# Sheet1.net
KiCad netlist of a schematic drawn in Altium Designer
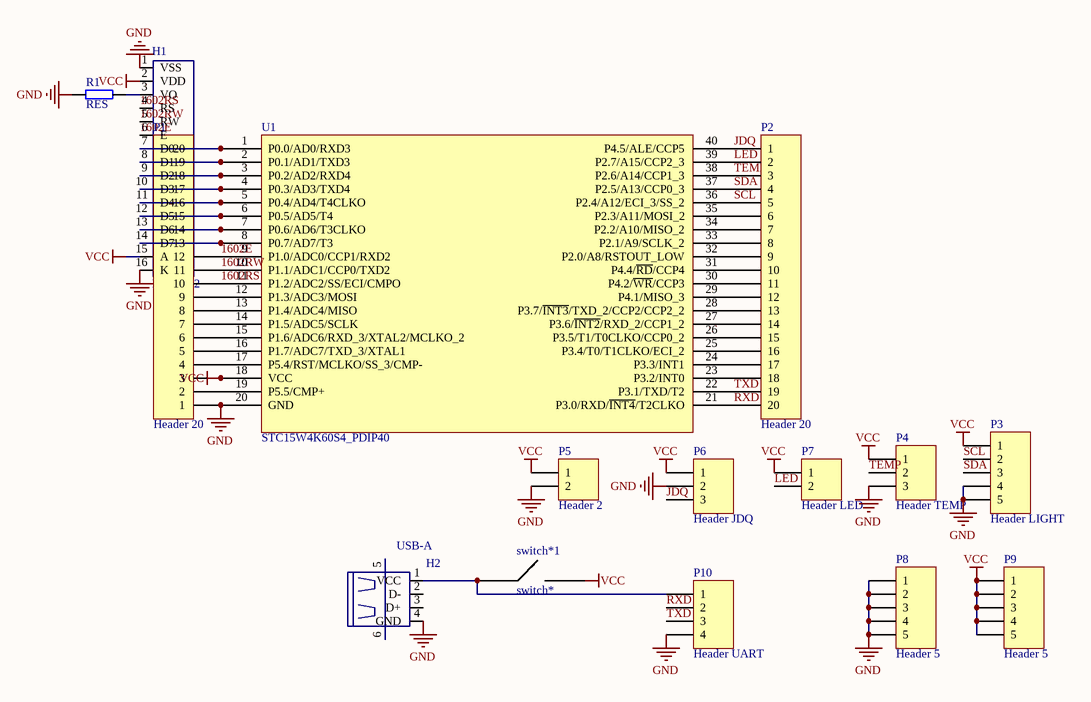
[diagram p0: Sheet1.SchDoc]

(export (version "E")
  (design (tool "Eeschema 10.0.6"))
  (components
    (comp (ref "H1") (value "LCD1602") (footprint "H_LCD(1602)") (libsource (lib "IC_Any") (part "LCD1602")))
    (comp (ref "H2") (value "USB-A") (footprint "USB-A") (libsource (lib "hxl") (part "USB-A")))
    (comp (ref "P1")
      (value "Header 20")
      (footprint "HDR1X20")
      (description "Header, 20-Pin")
      (fields (field (name "PUBLISHER") "Altium Limited"))
      (libsource (lib "") (part "Header 20_1"))
    )
    (comp (ref "P2")
      (value "Header 20")
      (footprint "HDR1X20")
      (description "Header, 20-Pin")
      (fields (field (name "PUBLISHER") "Altium Limited"))
      (libsource (lib "Miscellaneous Connectors") (part "Header 20"))
    )
    (comp (ref "P3")
      (value "Header LIGHT")
      (footprint "HDR1X5")
      (description "Header, 5-Pin")
      (fields (field (name "PUBLISHER") "Altium Limited"))
      (libsource (lib "Miscellaneous Connectors") (part "Header 5"))
    )
    (comp (ref "P4")
      (value "Header TEMP")
      (footprint "HDR1X3")
      (description "Header, 3-Pin")
      (fields (field (name "PUBLISHER") "Altium Limited"))
      (libsource (lib "Miscellaneous Connectors") (part "Header 3"))
    )
    (comp (ref "P5")
      (value "Header 2")
      (footprint "HDR1X2")
      (description "Header, 2-Pin")
      (fields (field (name "PUBLISHER") "Altium Limited"))
      (libsource (lib "Miscellaneous Connectors") (part "Header 2"))
    )
    (comp (ref "P6")
      (value "Header JDQ")
      (footprint "HDR1X3")
      (description "Header, 3-Pin")
      (fields (field (name "PUBLISHER") "Altium Limited"))
      (libsource (lib "Miscellaneous Connectors") (part "Header 3"))
    )
    (comp (ref "P7")
      (value "Header LED")
      (footprint "HDR1X2")
      (description "Header, 2-Pin")
      (fields (field (name "PUBLISHER") "Altium Limited"))
      (libsource (lib "Miscellaneous Connectors") (part "Header 2"))
    )
    (comp (ref "P8")
      (value "Header 5")
      (footprint "HDR1X5")
      (description "Header, 5-Pin")
      (fields (field (name "PUBLISHER") "Altium Limited"))
      (libsource (lib "Miscellaneous Connectors") (part "Header 5"))
    )
    (comp (ref "P9")
      (value "Header 5")
      (footprint "HDR1X5")
      (description "Header, 5-Pin")
      (fields (field (name "PUBLISHER") "Altium Limited"))
      (libsource (lib "Miscellaneous Connectors") (part "Header 5"))
    )
    (comp (ref "P10")
      (value "Header UART")
      (footprint "HDR1X4")
      (description "Header, 4-Pin")
      (fields (field (name "PUBLISHER") "Altium Limited"))
      (libsource (lib "Miscellaneous Connectors") (part "Header 4"))
    )
    (comp (ref "R1") (value "RES") (footprint "RES_IP") (libsource (lib "hxl") (part "RES")))
    (comp (ref "switch*1") (value "switch*") (footprint "switch") (libsource (lib "hxl") (part "switch")))
    (comp (ref "U1")
      (value "STC15W4K60S4_PDIP40")
      (footprint "DIP40")
      (libsource (lib "stcmcu_altium_lib") (part "STC15W4K60S4_PDIP40"))
    )
  )
  (nets
    (net (code "1") (name "/1602E") (class "Default")
      (node (ref "H1") (pin "6") (pinfunction "E_6") (pintype "passive"))
      (node (ref "P1") (pin "12") (pinfunction "12_12") (pintype "passive"))
      (node (ref "U1") (pin "9") (pinfunction "P1.0/ADC0/CCP1/RXD2_9") (pintype "passive"))
    )
    (net (code "2") (name "/1602RS") (class "Default")
      (node (ref "H1") (pin "4") (pinfunction "RS_4") (pintype "passive"))
      (node (ref "P1") (pin "10") (pinfunction "10_10") (pintype "passive"))
      (node (ref "U1") (pin "11") (pinfunction "P1.2/ADC2/SS/ECI/CMPO_11") (pintype "passive"))
    )
    (net (code "3") (name "/1602RW") (class "Default")
      (node (ref "H1") (pin "5") (pinfunction "RW_5") (pintype "passive"))
      (node (ref "P1") (pin "11") (pinfunction "11_11") (pintype "passive"))
      (node (ref "U1") (pin "10") (pinfunction "P1.1/ADC1/CCP0/TXD2_10") (pintype "passive"))
    )
    (net (code "4") (name "/JDQ") (class "Default")
      (node (ref "P2") (pin "1") (pinfunction "1_1") (pintype "passive"))
      (node (ref "P6") (pin "3") (pinfunction "3_3") (pintype "passive"))
      (node (ref "U1") (pin "40") (pinfunction "P4.5/ALE/CCP5_40") (pintype "passive"))
    )
    (net (code "5") (name "/LED") (class "Default")
      (node (ref "P2") (pin "2") (pinfunction "2_2") (pintype "passive"))
      (node (ref "P7") (pin "2") (pinfunction "2_2") (pintype "passive"))
      (node (ref "U1") (pin "39") (pinfunction "P2.7/A15/CCP2_3_39") (pintype "passive"))
    )
    (net (code "6") (name "/RXD") (class "Default")
      (node (ref "P10") (pin "2") (pinfunction "2_2") (pintype "passive"))
      (node (ref "P2") (pin "20") (pinfunction "20_20") (pintype "passive"))
      (node (ref "U1") (pin "21") (pinfunction "P3.0/RXD/~{INT4}/T2CLKO_21") (pintype "passive"))
    )
    (net (code "7") (name "/SCL") (class "Default")
      (node (ref "P2") (pin "5") (pinfunction "5_5") (pintype "passive"))
      (node (ref "P3") (pin "2") (pinfunction "2_2") (pintype "passive"))
      (node (ref "U1") (pin "36") (pinfunction "P2.4/A12/ECI_3/SS_2_36") (pintype "passive"))
    )
    (net (code "8") (name "/SDA") (class "Default")
      (node (ref "P2") (pin "4") (pinfunction "4_4") (pintype "passive"))
      (node (ref "P3") (pin "3") (pinfunction "3_3") (pintype "passive"))
      (node (ref "U1") (pin "37") (pinfunction "P2.5/A13/CCP0_3_37") (pintype "passive"))
    )
    (net (code "9") (name "/TEMP") (class "Default")
      (node (ref "P2") (pin "3") (pinfunction "3_3") (pintype "passive"))
      (node (ref "P4") (pin "2") (pinfunction "2_2") (pintype "passive"))
      (node (ref "U1") (pin "38") (pinfunction "P2.6/A14/CCP1_3_38") (pintype "passive"))
    )
    (net (code "10") (name "/TXD") (class "Default")
      (node (ref "P10") (pin "3") (pinfunction "3_3") (pintype "passive"))
      (node (ref "P2") (pin "19") (pinfunction "19_19") (pintype "passive"))
      (node (ref "U1") (pin "22") (pinfunction "P3.1/TXD/T2_22") (pintype "passive"))
    )
    (net (code "11") (name "GND") (class "Default")
      (node (ref "H1") (pin "1") (pinfunction "VSS_1") (pintype "passive"))
      (node (ref "H1") (pin "16") (pinfunction "K_16") (pintype "passive"))
      (node (ref "H2") (pin "4") (pinfunction "GND_4") (pintype "passive"))
      (node (ref "P1") (pin "1") (pinfunction "1_1") (pintype "passive"))
      (node (ref "P10") (pin "4") (pinfunction "4_4") (pintype "passive"))
      (node (ref "P3") (pin "4") (pinfunction "4_4") (pintype "passive"))
      (node (ref "P3") (pin "5") (pinfunction "5_5") (pintype "passive"))
      (node (ref "P4") (pin "3") (pinfunction "3_3") (pintype "passive"))
      (node (ref "P5") (pin "2") (pinfunction "2_2") (pintype "passive"))
      (node (ref "P6") (pin "2") (pinfunction "2_2") (pintype "passive"))
      (node (ref "P8") (pin "1") (pinfunction "1_1") (pintype "passive"))
      (node (ref "P8") (pin "2") (pinfunction "2_2") (pintype "passive"))
      (node (ref "P8") (pin "3") (pinfunction "3_3") (pintype "passive"))
      (node (ref "P8") (pin "4") (pinfunction "4_4") (pintype "passive"))
      (node (ref "P8") (pin "5") (pinfunction "5_5") (pintype "passive"))
      (node (ref "R1") (pin "1") (pinfunction "1_1") (pintype "passive"))
      (node (ref "U1") (pin "20") (pinfunction "GND_20") (pintype "passive"))
    )
    (net (code "12") (name "Net-(H1-D0)") (class "Default")
      (node (ref "H1") (pin "7") (pinfunction "D0_7") (pintype "passive"))
      (node (ref "P1") (pin "20") (pinfunction "20_20") (pintype "passive"))
      (node (ref "U1") (pin "1") (pinfunction "P0.0/AD0/RXD3_1") (pintype "passive"))
    )
    (net (code "13") (name "Net-(H1-D1)") (class "Default")
      (node (ref "H1") (pin "8") (pinfunction "D1_8") (pintype "passive"))
      (node (ref "P1") (pin "19") (pinfunction "19_19") (pintype "passive"))
      (node (ref "U1") (pin "2") (pinfunction "P0.1/AD1/TXD3_2") (pintype "passive"))
    )
    (net (code "14") (name "Net-(H1-D2)") (class "Default")
      (node (ref "H1") (pin "9") (pinfunction "D2_9") (pintype "passive"))
      (node (ref "P1") (pin "18") (pinfunction "18_18") (pintype "passive"))
      (node (ref "U1") (pin "3") (pinfunction "P0.2/AD2/RXD4_3") (pintype "passive"))
    )
    (net (code "15") (name "Net-(H1-D3)") (class "Default")
      (node (ref "H1") (pin "10") (pinfunction "D3_10") (pintype "passive"))
      (node (ref "P1") (pin "17") (pinfunction "17_17") (pintype "passive"))
      (node (ref "U1") (pin "4") (pinfunction "P0.3/AD3/TXD4_4") (pintype "passive"))
    )
    (net (code "16") (name "Net-(H1-D4)") (class "Default")
      (node (ref "H1") (pin "11") (pinfunction "D4_11") (pintype "passive"))
      (node (ref "P1") (pin "16") (pinfunction "16_16") (pintype "passive"))
      (node (ref "U1") (pin "5") (pinfunction "P0.4/AD4/T4CLKO_5") (pintype "passive"))
    )
    (net (code "17") (name "Net-(H1-D5)") (class "Default")
      (node (ref "H1") (pin "12") (pinfunction "D5_12") (pintype "passive"))
      (node (ref "P1") (pin "15") (pinfunction "15_15") (pintype "passive"))
      (node (ref "U1") (pin "6") (pinfunction "P0.5/AD5/T4_6") (pintype "passive"))
    )
    (net (code "18") (name "Net-(H1-D6)") (class "Default")
      (node (ref "H1") (pin "13") (pinfunction "D6_13") (pintype "passive"))
      (node (ref "P1") (pin "14") (pinfunction "14_14") (pintype "passive"))
      (node (ref "U1") (pin "7") (pinfunction "P0.6/AD6/T3CLKO_7") (pintype "passive"))
    )
    (net (code "19") (name "Net-(H1-D7)") (class "Default")
      (node (ref "H1") (pin "14") (pinfunction "D7_14") (pintype "passive"))
      (node (ref "P1") (pin "13") (pinfunction "13_13") (pintype "passive"))
      (node (ref "U1") (pin "8") (pinfunction "P0.7/AD7/T3_8") (pintype "passive"))
    )
    (net (code "20") (name "Net-(H1-VO)") (class "Default")
      (node (ref "H1") (pin "3") (pinfunction "VO_3") (pintype "passive"))
      (node (ref "R1") (pin "2") (pinfunction "2_2") (pintype "passive"))
    )
    (net (code "21") (name "Net-(H2-Pad5)") (class "Default")
      (node (ref "H2") (pin "5") (pinfunction "5_5") (pintype "passive"))
      (node (ref "H2") (pin "6") (pinfunction "6_6") (pintype "passive"))
    )
    (net (code "22") (name "Net-(H2-VCC)") (class "Default")
      (node (ref "H2") (pin "1") (pinfunction "VCC_1") (pintype "passive"))
      (node (ref "P10") (pin "1") (pinfunction "1_1") (pintype "passive"))
      (node (ref "switch*1") (pin "0") (pinfunction "0_0") (pintype "passive"))
    )
    (net (code "23") (name "Net-(U1-P1.3{slash}ADC3{slash}MOSI)") (class "Default")
      (node (ref "P1") (pin "9") (pinfunction "9_9") (pintype "passive"))
      (node (ref "U1") (pin "12") (pinfunction "P1.3/ADC3/MOSI_12") (pintype "passive"))
    )
    (net (code "24") (name "Net-(U1-P1.4{slash}ADC4{slash}MISO)") (class "Default")
      (node (ref "P1") (pin "8") (pinfunction "8_8") (pintype "passive"))
      (node (ref "U1") (pin "13") (pinfunction "P1.4/ADC4/MISO_13") (pintype "passive"))
    )
    (net (code "25") (name "Net-(U1-P1.5{slash}ADC5{slash}SCLK)") (class "Default")
      (node (ref "P1") (pin "7") (pinfunction "7_7") (pintype "passive"))
      (node (ref "U1") (pin "14") (pinfunction "P1.5/ADC5/SCLK_14") (pintype "passive"))
    )
    (net (code "26") (name "Net-(U1-P1.6{slash}ADC6{slash}RXD_3{slash}XTAL2{slash}MCLKO_2)") (class "Default")
      (node (ref "P1") (pin "6") (pinfunction "6_6") (pintype "passive"))
      (node (ref "U1") (pin "15") (pinfunction "P1.6/ADC6/RXD_3/XTAL2/MCLKO_2_15") (pintype "passive"))
    )
    (net (code "27") (name "Net-(U1-P1.7{slash}ADC7{slash}TXD_3{slash}XTAL1)") (class "Default")
      (node (ref "P1") (pin "5") (pinfunction "5_5") (pintype "passive"))
      (node (ref "U1") (pin "16") (pinfunction "P1.7/ADC7/TXD_3/XTAL1_16") (pintype "passive"))
    )
    (net (code "28") (name "Net-(U1-P2.0{slash}A8{slash}RSTOUT_LOW)") (class "Default")
      (node (ref "P2") (pin "9") (pinfunction "9_9") (pintype "passive"))
      (node (ref "U1") (pin "32") (pinfunction "P2.0/A8/RSTOUT_LOW_32") (pintype "passive"))
    )
    (net (code "29") (name "Net-(U1-P2.1{slash}A9{slash}SCLK_2)") (class "Default")
      (node (ref "P2") (pin "8") (pinfunction "8_8") (pintype "passive"))
      (node (ref "U1") (pin "33") (pinfunction "P2.1/A9/SCLK_2_33") (pintype "passive"))
    )
    (net (code "30") (name "Net-(U1-P2.2{slash}A10{slash}MISO_2)") (class "Default")
      (node (ref "P2") (pin "7") (pinfunction "7_7") (pintype "passive"))
      (node (ref "U1") (pin "34") (pinfunction "P2.2/A10/MISO_2_34") (pintype "passive"))
    )
    (net (code "31") (name "Net-(U1-P2.3{slash}A11{slash}MOSI_2)") (class "Default")
      (node (ref "P2") (pin "6") (pinfunction "6_6") (pintype "passive"))
      (node (ref "U1") (pin "35") (pinfunction "P2.3/A11/MOSI_2_35") (pintype "passive"))
    )
    (net (code "32") (name "Net-(U1-P3.2{slash}INT0)") (class "Default")
      (node (ref "P2") (pin "18") (pinfunction "18_18") (pintype "passive"))
      (node (ref "U1") (pin "23") (pinfunction "P3.2/INT0_23") (pintype "passive"))
    )
    (net (code "33") (name "Net-(U1-P3.3{slash}INT1)") (class "Default")
      (node (ref "P2") (pin "17") (pinfunction "17_17") (pintype "passive"))
      (node (ref "U1") (pin "24") (pinfunction "P3.3/INT1_24") (pintype "passive"))
    )
    (net (code "34") (name "Net-(U1-P3.4{slash}T0{slash}T1CLKO{slash}ECI_2)") (class "Default")
      (node (ref "P2") (pin "16") (pinfunction "16_16") (pintype "passive"))
      (node (ref "U1") (pin "25") (pinfunction "P3.4/T0/T1CLKO/ECI_2_25") (pintype "passive"))
    )
    (net (code "35") (name "Net-(U1-P3.5{slash}T1{slash}T0CLKO{slash}CCP0_2)") (class "Default")
      (node (ref "P2") (pin "15") (pinfunction "15_15") (pintype "passive"))
      (node (ref "U1") (pin "26") (pinfunction "P3.5/T1/T0CLKO/CCP0_2_26") (pintype "passive"))
    )
    (net (code "36") (name "Net-(U1-P3.6{slash}~{INT2}{slash}RXD_2{slash}CCP1_2)") (class "Default")
      (node (ref "P2") (pin "14") (pinfunction "14_14") (pintype "passive"))
      (node (ref "U1") (pin "27") (pinfunction "P3.6/~{INT2}/RXD_2/CCP1_2_27") (pintype "passive"))
    )
    (net (code "37") (name "Net-(U1-P3.7{slash}~{INT3}{slash}TXD_2{slash}CCP2{slash}CCP2_2)") (class "Default")
      (node (ref "P2") (pin "13") (pinfunction "13_13") (pintype "passive"))
      (node (ref "U1") (pin "28") (pinfunction "P3.7/~{INT3}/TXD_2/CCP2/CCP2_2_28") (pintype "passive"))
    )
    (net (code "38") (name "Net-(U1-P4.1{slash}MISO_3)") (class "Default")
      (node (ref "P2") (pin "12") (pinfunction "12_12") (pintype "passive"))
      (node (ref "U1") (pin "29") (pinfunction "P4.1/MISO_3_29") (pintype "passive"))
    )
    (net (code "39") (name "Net-(U1-P4.2{slash}~{WR}{slash}CCP3)") (class "Default")
      (node (ref "P2") (pin "11") (pinfunction "11_11") (pintype "passive"))
      (node (ref "U1") (pin "30") (pinfunction "P4.2/~{WR}/CCP3_30") (pintype "passive"))
    )
    (net (code "40") (name "Net-(U1-P4.4{slash}~{RD}{slash}CCP4)") (class "Default")
      (node (ref "P2") (pin "10") (pinfunction "10_10") (pintype "passive"))
      (node (ref "U1") (pin "31") (pinfunction "P4.4/~{RD}/CCP4_31") (pintype "passive"))
    )
    (net (code "41") (name "Net-(U1-P5.4{slash}RST{slash}MCLKO{slash}SS_3{slash}CMP-)") (class "Default")
      (node (ref "P1") (pin "4") (pinfunction "4_4") (pintype "passive"))
      (node (ref "U1") (pin "17") (pinfunction "P5.4/RST/MCLKO/SS_3/CMP-_17") (pintype "passive"))
    )
    (net (code "42") (name "Net-(U1-P5.5{slash}CMP+)") (class "Default")
      (node (ref "P1") (pin "2") (pinfunction "2_2") (pintype "passive"))
      (node (ref "U1") (pin "19") (pinfunction "P5.5/CMP+_19") (pintype "passive"))
    )
    (net (code "43") (name "VCC") (class "Default")
      (node (ref "H1") (pin "15") (pinfunction "A_15") (pintype "passive"))
      (node (ref "H1") (pin "2") (pinfunction "VDD_2") (pintype "passive"))
      (node (ref "P1") (pin "3") (pinfunction "3_3") (pintype "passive"))
      (node (ref "P3") (pin "1") (pinfunction "1_1") (pintype "passive"))
      (node (ref "P4") (pin "1") (pinfunction "1_1") (pintype "passive"))
      (node (ref "P5") (pin "1") (pinfunction "1_1") (pintype "passive"))
      (node (ref "P6") (pin "1") (pinfunction "1_1") (pintype "passive"))
      (node (ref "P7") (pin "1") (pinfunction "1_1") (pintype "passive"))
      (node (ref "P9") (pin "1") (pinfunction "1_1") (pintype "passive"))
      (node (ref "P9") (pin "2") (pinfunction "2_2") (pintype "passive"))
      (node (ref "P9") (pin "3") (pinfunction "3_3") (pintype "passive"))
      (node (ref "P9") (pin "4") (pinfunction "4_4") (pintype "passive"))
      (node (ref "P9") (pin "5") (pinfunction "5_5") (pintype "passive"))
      (node (ref "U1") (pin "18") (pinfunction "VCC_18") (pintype "passive"))
      (node (ref "switch*1") (pin "1") (pinfunction "1_1") (pintype "passive"))
    )
    (net (code "44") (name "unconnected-(H2-D+-Pad3)") (class "Default")
      (node (ref "H2") (pin "3") (pinfunction "D+_3") (pintype "passive"))
    )
    (net (code "45") (name "unconnected-(H2-D--Pad2)") (class "Default")
      (node (ref "H2") (pin "2") (pinfunction "D-_2") (pintype "passive"))
    )
  )
)
